# master_schematic.net
KiCad netlist of a schematic drawn in EAGLE
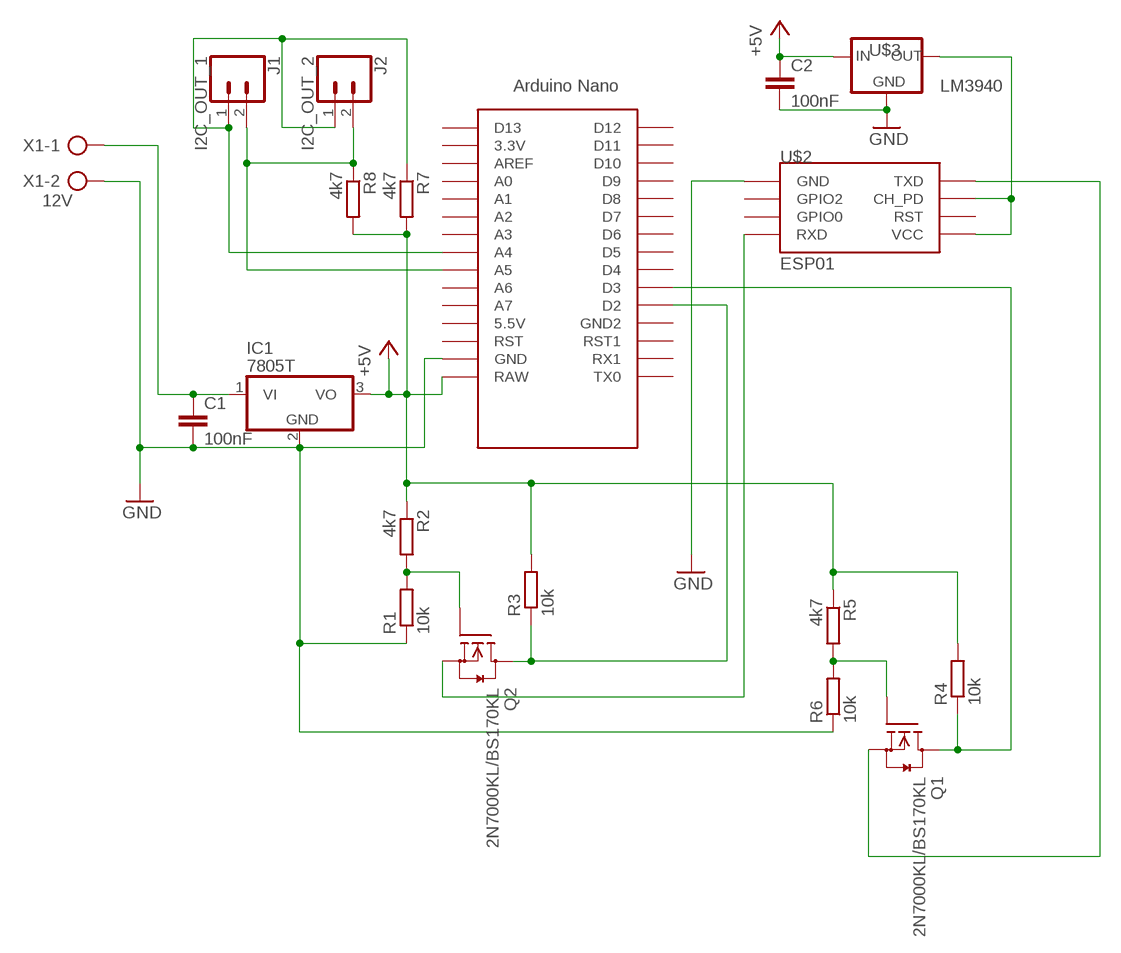
[diagram p0: schematic, sheet 1]

(export (version "E")
  (design (tool "Eeschema 10.0.6"))
  (components
    (comp (ref "C1")
      (value "100nF")
      (footprint "eagle-import:C025-030X050")
      (libsource (lib "eagle-import") (part "C-EU025-030X050"))
    )
    (comp (ref "C2")
      (value "100nF")
      (footprint "eagle-import:C025-030X050")
      (libsource (lib "eagle-import") (part "C-EU025-030X050"))
    )
    (comp (ref "IC1")
      (value "7805T")
      (footprint "eagle-import:TO220H")
      (libsource (lib "eagle-import") (part "78T05"))
    )
    (comp (ref "J1")
      (value "I2C_OUT_1")
      (footprint "eagle-import:JST-2-PTH")
      (libsource (lib "eagle-import") (part "CONN_02JST-PTH-2"))
    )
    (comp (ref "J2")
      (value "I2C_OUT_2")
      (footprint "eagle-import:JST-2-PTH")
      (libsource (lib "eagle-import") (part "CONN_02JST-PTH-2"))
    )
    (comp (ref "Q1")
      (value "2N7000KL/BS170KL")
      (footprint "eagle-import:TO92")
      (libsource (lib "eagle-import") (part "2N7000KL/BS170KL"))
    )
    (comp (ref "Q2")
      (value "2N7000KL/BS170KL")
      (footprint "eagle-import:TO92")
      (libsource (lib "eagle-import") (part "2N7000KL/BS170KL"))
    )
    (comp (ref "R1")
      (value "10k")
      (footprint "eagle-import:0207_10")
      (libsource (lib "eagle-import") (part "R-EU_0207/10"))
    )
    (comp (ref "R2")
      (value "4k7")
      (footprint "eagle-import:0207_10")
      (libsource (lib "eagle-import") (part "R-EU_0207/10"))
    )
    (comp (ref "R3")
      (value "10k")
      (footprint "eagle-import:0207_10")
      (libsource (lib "eagle-import") (part "R-EU_0207/10"))
    )
    (comp (ref "R4")
      (value "10k")
      (footprint "eagle-import:0207_10")
      (libsource (lib "eagle-import") (part "R-EU_0207/10"))
    )
    (comp (ref "R5")
      (value "4k7")
      (footprint "eagle-import:0207_10")
      (libsource (lib "eagle-import") (part "R-EU_0207/10"))
    )
    (comp (ref "R6")
      (value "10k")
      (footprint "eagle-import:0207_10")
      (libsource (lib "eagle-import") (part "R-EU_0207/10"))
    )
    (comp (ref "R7")
      (value "4k7")
      (footprint "eagle-import:0207_10")
      (libsource (lib "eagle-import") (part "R-EU_0207/10"))
    )
    (comp (ref "R8")
      (value "4k7")
      (footprint "eagle-import:0207_10")
      (libsource (lib "eagle-import") (part "R-EU_0207/10"))
    )
    (comp (ref "U$1")
      (value "NANO")
      (footprint "eagle-import:NANO")
      (libsource (lib "eagle-import") (part "NANO"))
    )
    (comp (ref "U$2")
      (value "ESP01")
      (footprint "eagle-import:ESP01")
      (libsource (lib "eagle-import") (part "ESP01"))
    )
    (comp (ref "U$3")
      (value "LM3940")
      (footprint "eagle-import:TO220")
      (fields (field (name "MF") "National Semiconductor"))
      (libsource (lib "eagle-import") (part "LM3940"))
    )
    (comp (ref "X1")
      (value "12V")
      (footprint "eagle-import:AK300_2")
      (libsource (lib "eagle-import") (part "AK300/2"))
    )
  )
  (nets
    (net (code "1") (name "+5V") (class "Default")
      (node (ref "C2") (pin "1") (pinfunction "1_1") (pintype "passive"))
      (node (ref "IC1") (pin "3") (pinfunction "VO_3") (pintype "passive"))
      (node (ref "R2") (pin "1") (pinfunction "1_1") (pintype "passive"))
      (node (ref "R3") (pin "2") (pinfunction "2_2") (pintype "passive"))
      (node (ref "R4") (pin "2") (pinfunction "2_2") (pintype "passive"))
      (node (ref "R5") (pin "1") (pinfunction "1_1") (pintype "passive"))
      (node (ref "R7") (pin "2") (pinfunction "2_2") (pintype "passive"))
      (node (ref "R8") (pin "2") (pinfunction "2_2") (pintype "passive"))
      (node (ref "U$1") (pin "RAW") (pinfunction "RAW_RAW") (pintype "bidirectional"))
      (node (ref "U$3") (pin "1") (pinfunction "IN_1") (pintype "input"))
    )
    (net (code "2") (name "GND") (class "Default")
      (node (ref "C1") (pin "2") (pinfunction "2_2") (pintype "passive"))
      (node (ref "C2") (pin "2") (pinfunction "2_2") (pintype "passive"))
      (node (ref "IC1") (pin "2") (pinfunction "GND_2") (pintype "passive"))
      (node (ref "R1") (pin "1") (pinfunction "1_1") (pintype "passive"))
      (node (ref "R6") (pin "1") (pinfunction "1_1") (pintype "passive"))
      (node (ref "U$1") (pin "GND") (pinfunction "GND_GND") (pintype "bidirectional"))
      (node (ref "U$2") (pin "GND") (pinfunction "GND_GND") (pintype "bidirectional"))
      (node (ref "U$3") (pin "2") (pinfunction "GND_2") (pintype "input"))
      (node (ref "X1") (pin "2") (pinfunction "KL_2") (pintype "passive"))
    )
    (net (code "3") (name "Net-(IC1-VI)") (class "Default")
      (node (ref "C1") (pin "1") (pinfunction "1_1") (pintype "passive"))
      (node (ref "IC1") (pin "1") (pinfunction "VI_1") (pintype "input"))
      (node (ref "X1") (pin "1") (pinfunction "KL_1") (pintype "passive"))
    )
    (net (code "4") (name "Net-(J1-Pad1)") (class "Default")
      (node (ref "J1") (pin "1") (pinfunction "1_1") (pintype "passive"))
      (node (ref "J2") (pin "1") (pinfunction "1_1") (pintype "passive"))
      (node (ref "R7") (pin "1") (pinfunction "1_1") (pintype "passive"))
      (node (ref "U$1") (pin "A4") (pinfunction "A4_A4") (pintype "bidirectional"))
    )
    (net (code "5") (name "Net-(J1-Pad2)") (class "Default")
      (node (ref "J1") (pin "2") (pinfunction "2_2") (pintype "passive"))
      (node (ref "J2") (pin "2") (pinfunction "2_2") (pintype "passive"))
      (node (ref "R8") (pin "1") (pinfunction "1_1") (pintype "passive"))
      (node (ref "U$1") (pin "A5") (pinfunction "A5_A5") (pintype "bidirectional"))
    )
    (net (code "6") (name "Net-(Q1-D)") (class "Default")
      (node (ref "Q1") (pin "3") (pinfunction "D_3") (pintype "passive"))
      (node (ref "R4") (pin "1") (pinfunction "1_1") (pintype "passive"))
      (node (ref "U$1") (pin "D3") (pinfunction "D3_D3") (pintype "bidirectional"))
    )
    (net (code "7") (name "Net-(Q1-G)") (class "Default")
      (node (ref "Q1") (pin "2") (pinfunction "G_2") (pintype "passive"))
      (node (ref "R5") (pin "2") (pinfunction "2_2") (pintype "passive"))
      (node (ref "R6") (pin "2") (pinfunction "2_2") (pintype "passive"))
    )
    (net (code "8") (name "Net-(Q1-S)") (class "Default")
      (node (ref "Q1") (pin "1") (pinfunction "S_1") (pintype "passive"))
      (node (ref "U$2") (pin "TX") (pinfunction "TXD_TX") (pintype "bidirectional"))
    )
    (net (code "9") (name "Net-(Q2-D)") (class "Default")
      (node (ref "Q2") (pin "3") (pinfunction "D_3") (pintype "passive"))
      (node (ref "R3") (pin "1") (pinfunction "1_1") (pintype "passive"))
      (node (ref "U$1") (pin "D2") (pinfunction "D2_D2") (pintype "bidirectional"))
    )
    (net (code "10") (name "Net-(Q2-G)") (class "Default")
      (node (ref "Q2") (pin "2") (pinfunction "G_2") (pintype "passive"))
      (node (ref "R1") (pin "2") (pinfunction "2_2") (pintype "passive"))
      (node (ref "R2") (pin "2") (pinfunction "2_2") (pintype "passive"))
    )
    (net (code "11") (name "Net-(Q2-S)") (class "Default")
      (node (ref "Q2") (pin "1") (pinfunction "S_1") (pintype "passive"))
      (node (ref "U$2") (pin "RX") (pinfunction "RXD_RX") (pintype "bidirectional"))
    )
    (net (code "12") (name "Net-(U$3-OUT)") (class "Default")
      (node (ref "U$2") (pin "CH_PD") (pinfunction "CH_PD_CH_PD") (pintype "bidirectional"))
      (node (ref "U$2") (pin "VCC") (pinfunction "VCC_VCC") (pintype "bidirectional"))
      (node (ref "U$3") (pin "3") (pinfunction "OUT_3") (pintype "output"))
    )
    (net (code "13") (name "unconnected-(U$1-5.5V-Pad5V)") (class "Default")
      (node (ref "U$1") (pin "5V") (pinfunction "5.5V_5V") (pintype "bidirectional"))
    )
    (net (code "14") (name "unconnected-(U$1-GND2-PadGND1)") (class "Default")
      (node (ref "U$1") (pin "GND1") (pinfunction "GND2_GND1") (pintype "bidirectional"))
    )
    (net (code "15") (name "unconnected-(U$1-Pad3.3V)") (class "Default")
      (node (ref "U$1") (pin "3.3V") (pinfunction "3.3V_3.3V") (pintype "bidirectional"))
    )
    (net (code "16") (name "unconnected-(U$1-PadA0)") (class "Default")
      (node (ref "U$1") (pin "A0") (pinfunction "A0_A0") (pintype "bidirectional"))
    )
    (net (code "17") (name "unconnected-(U$1-PadA1)") (class "Default")
      (node (ref "U$1") (pin "A1") (pinfunction "A1_A1") (pintype "bidirectional"))
    )
    (net (code "18") (name "unconnected-(U$1-PadA2)") (class "Default")
      (node (ref "U$1") (pin "A2") (pinfunction "A2_A2") (pintype "bidirectional"))
    )
    (net (code "19") (name "unconnected-(U$1-PadA3)") (class "Default")
      (node (ref "U$1") (pin "A3") (pinfunction "A3_A3") (pintype "bidirectional"))
    )
    (net (code "20") (name "unconnected-(U$1-PadA6)") (class "Default")
      (node (ref "U$1") (pin "A6") (pinfunction "A6_A6") (pintype "bidirectional"))
    )
    (net (code "21") (name "unconnected-(U$1-PadA7)") (class "Default")
      (node (ref "U$1") (pin "A7") (pinfunction "A7_A7") (pintype "bidirectional"))
    )
    (net (code "22") (name "unconnected-(U$1-PadAREF)") (class "Default")
      (node (ref "U$1") (pin "AREF") (pinfunction "AREF_AREF") (pintype "bidirectional"))
    )
    (net (code "23") (name "unconnected-(U$1-PadD4)") (class "Default")
      (node (ref "U$1") (pin "D4") (pinfunction "D4_D4") (pintype "bidirectional"))
    )
    (net (code "24") (name "unconnected-(U$1-PadD5)") (class "Default")
      (node (ref "U$1") (pin "D5") (pinfunction "D5_D5") (pintype "bidirectional"))
    )
    (net (code "25") (name "unconnected-(U$1-PadD6)") (class "Default")
      (node (ref "U$1") (pin "D6") (pinfunction "D6_D6") (pintype "bidirectional"))
    )
    (net (code "26") (name "unconnected-(U$1-PadD7)") (class "Default")
      (node (ref "U$1") (pin "D7") (pinfunction "D7_D7") (pintype "bidirectional"))
    )
    (net (code "27") (name "unconnected-(U$1-PadD8)") (class "Default")
      (node (ref "U$1") (pin "D8") (pinfunction "D8_D8") (pintype "bidirectional"))
    )
    (net (code "28") (name "unconnected-(U$1-PadD9)") (class "Default")
      (node (ref "U$1") (pin "D9") (pinfunction "D9_D9") (pintype "bidirectional"))
    )
    (net (code "29") (name "unconnected-(U$1-PadD10)") (class "Default")
      (node (ref "U$1") (pin "D10") (pinfunction "D10_D10") (pintype "bidirectional"))
    )
    (net (code "30") (name "unconnected-(U$1-PadD11)") (class "Default")
      (node (ref "U$1") (pin "D11") (pinfunction "D11_D11") (pintype "bidirectional"))
    )
    (net (code "31") (name "unconnected-(U$1-PadD12)") (class "Default")
      (node (ref "U$1") (pin "D12") (pinfunction "D12_D12") (pintype "bidirectional"))
    )
    (net (code "32") (name "unconnected-(U$1-PadD13)") (class "Default")
      (node (ref "U$1") (pin "D13") (pinfunction "D13_D13") (pintype "bidirectional"))
    )
    (net (code "33") (name "unconnected-(U$1-PadICSP1)") (class "Default")
      (node (ref "U$1") (pin "ICSP1") (pinfunction "ICSP1_ICSP1") (pintype "bidirectional"))
    )
    (net (code "34") (name "unconnected-(U$1-PadICSP2)") (class "Default")
      (node (ref "U$1") (pin "ICSP2") (pinfunction "ICSP2_ICSP2") (pintype "bidirectional"))
    )
    (net (code "35") (name "unconnected-(U$1-PadICSP3)") (class "Default")
      (node (ref "U$1") (pin "ICSP3") (pinfunction "ICSP3_ICSP3") (pintype "bidirectional"))
    )
    (net (code "36") (name "unconnected-(U$1-PadICSP4)") (class "Default")
      (node (ref "U$1") (pin "ICSP4") (pinfunction "ICSP4_ICSP4") (pintype "bidirectional"))
    )
    (net (code "37") (name "unconnected-(U$1-PadICSP5)") (class "Default")
      (node (ref "U$1") (pin "ICSP5") (pinfunction "ICSP5_ICSP5") (pintype "bidirectional"))
    )
    (net (code "38") (name "unconnected-(U$1-PadICSP6)") (class "Default")
      (node (ref "U$1") (pin "ICSP6") (pinfunction "ICSP6_ICSP6") (pintype "bidirectional"))
    )
    (net (code "39") (name "unconnected-(U$1-PadRST)") (class "Default")
      (node (ref "U$1") (pin "RST") (pinfunction "RST_RST") (pintype "bidirectional"))
    )
    (net (code "40") (name "unconnected-(U$1-PadRST1)") (class "Default")
      (node (ref "U$1") (pin "RST1") (pinfunction "RST1_RST1") (pintype "bidirectional"))
    )
    (net (code "41") (name "unconnected-(U$1-PadRX1)") (class "Default")
      (node (ref "U$1") (pin "RX1") (pinfunction "RX1_RX1") (pintype "bidirectional"))
    )
    (net (code "42") (name "unconnected-(U$1-PadTX0)") (class "Default")
      (node (ref "U$1") (pin "TX0") (pinfunction "TX0_TX0") (pintype "bidirectional"))
    )
    (net (code "43") (name "unconnected-(U$2-PadGPIO0)") (class "Default")
      (node (ref "U$2") (pin "GPIO0") (pinfunction "GPIO0_GPIO0") (pintype "bidirectional"))
    )
    (net (code "44") (name "unconnected-(U$2-PadGPIO2)") (class "Default")
      (node (ref "U$2") (pin "GPIO2") (pinfunction "GPIO2_GPIO2") (pintype "bidirectional"))
    )
    (net (code "45") (name "unconnected-(U$2-PadRST)") (class "Default")
      (node (ref "U$2") (pin "RST") (pinfunction "RST_RST") (pintype "bidirectional"))
    )
  )
)
